# temperatureSensor.net
KiCad netlist of a schematic drawn in Altium Designer
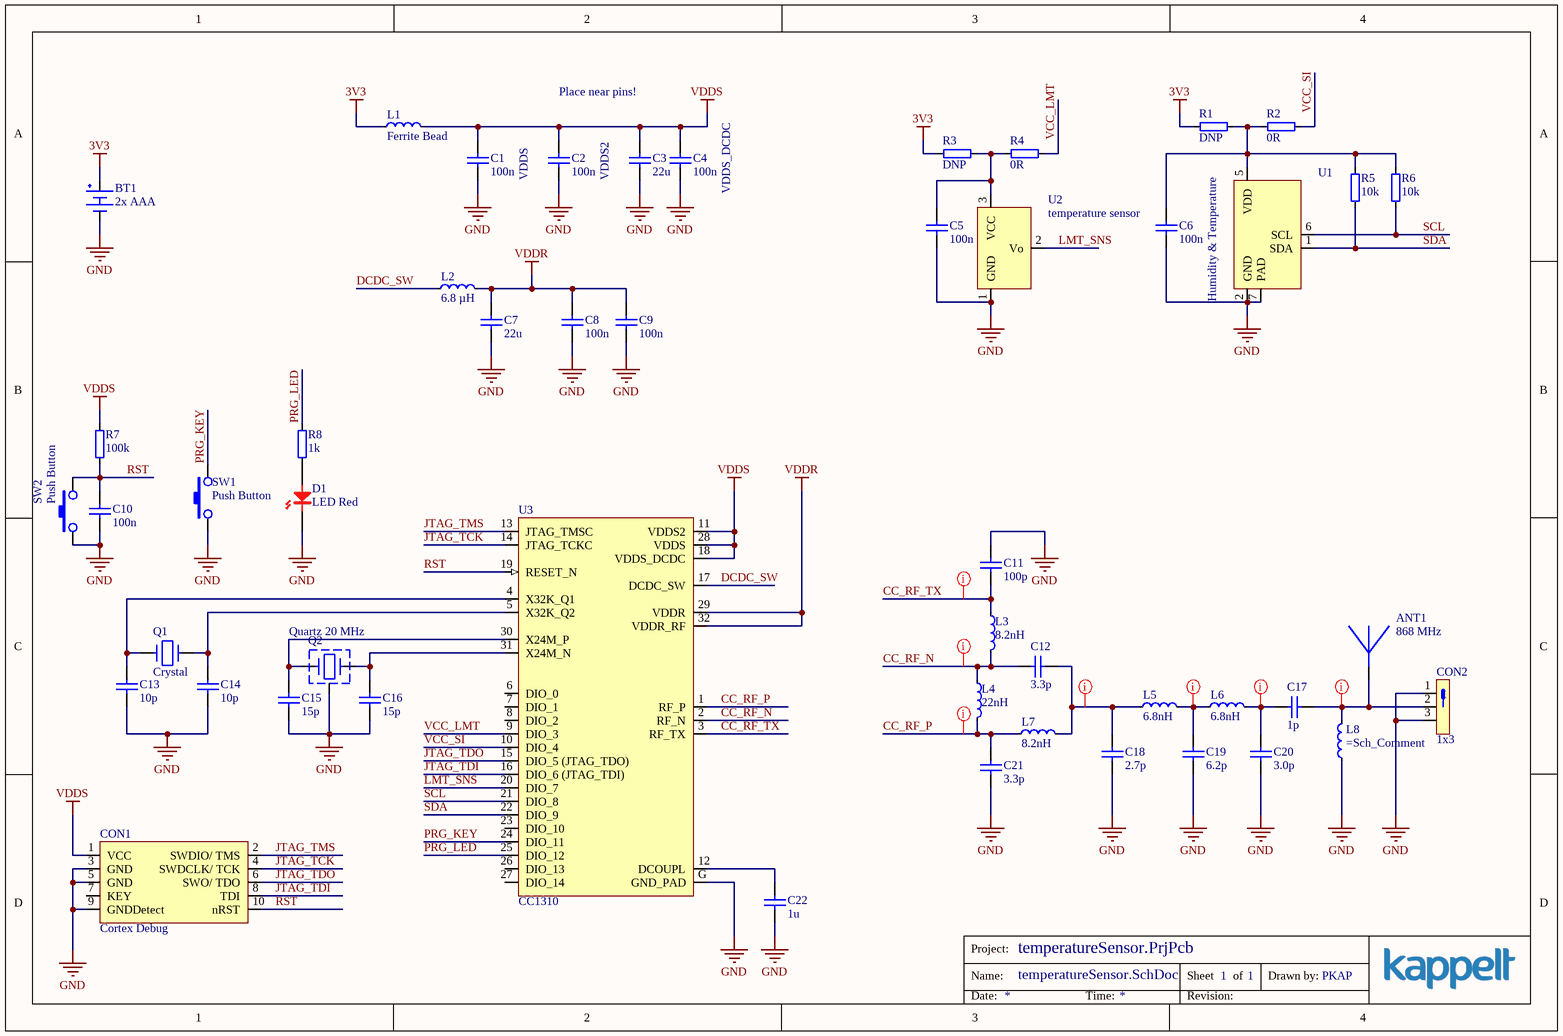
[diagram p0: temperatureSensor.SchDoc]

(export (version "E")
  (design (tool "Eeschema 10.0.6"))
  (components
    (comp (ref "ANT1")
      (value "868 MHz")
      (footprint "temperatureSensor:Ant-868-Helical")
      (description "868 MHz Helical PCB Antenna, see TI swra416.pdf")
      (libsource (lib "temperatureSensor") (part "ANT-868-Helical"))
    )
    (comp (ref "BT1")
      (value "2x AAA")
      (footprint "temperatureSensor:Keystone-2468")
      (description "Double AAA Battery Holder")
      (libsource (lib "temperatureSensor") (part "Battery-AAA-Double"))
    )
    (comp (ref "C1")
      (value "100n")
      (footprint "0603_N")
      (description "100n 50V 0603")
      (fields (field (name "PART NUMBER") "100n_50V_0603"))
      (libsource (lib "kappelt_altlib") (part "CAP_CERAMIC"))
    )
    (comp (ref "C2")
      (value "100n")
      (footprint "0603_N")
      (description "100n 50V 0603")
      (fields (field (name "PART NUMBER") "100n_50V_0603"))
      (libsource (lib "kappelt_altlib") (part "CAP_CERAMIC"))
    )
    (comp (ref "C3")
      (value "22u")
      (footprint "0805_N")
      (description "22u 25V 0805")
      (fields (field (name "PART NUMBER") "22u_25V_0805"))
      (libsource (lib "kappelt_altlib") (part "CAP_CERAMIC"))
    )
    (comp (ref "C4")
      (value "100n")
      (footprint "0603_N")
      (description "100n 50V 0603")
      (fields (field (name "PART NUMBER") "100n_50V_0603"))
      (libsource (lib "kappelt_altlib") (part "CAP_CERAMIC"))
    )
    (comp (ref "C5")
      (value "100n")
      (footprint "0603_N")
      (description "100n 50V 0603")
      (fields (field (name "PART NUMBER") "100n_50V_0603"))
      (libsource (lib "kappelt_altlib") (part "CAP_CERAMIC"))
    )
    (comp (ref "C6")
      (value "100n")
      (footprint "0603_N")
      (description "100n 50V 0603")
      (fields (field (name "PART NUMBER") "100n_50V_0603"))
      (libsource (lib "kappelt_altlib") (part "CAP_CERAMIC"))
    )
    (comp (ref "C7")
      (value "22u")
      (footprint "0805_N")
      (description "22u 25V 0805")
      (fields (field (name "PART NUMBER") "22u_25V_0805"))
      (libsource (lib "kappelt_altlib") (part "CAP_CERAMIC"))
    )
    (comp (ref "C8")
      (value "100n")
      (footprint "0603_N")
      (description "100n 50V 0603")
      (fields (field (name "PART NUMBER") "100n_50V_0603"))
      (libsource (lib "kappelt_altlib") (part "CAP_CERAMIC"))
    )
    (comp (ref "C9")
      (value "100n")
      (footprint "0603_N")
      (description "100n 50V 0603")
      (fields (field (name "PART NUMBER") "100n_50V_0603"))
      (libsource (lib "kappelt_altlib") (part "CAP_CERAMIC"))
    )
    (comp (ref "C10")
      (value "100n")
      (footprint "0603_N")
      (description "100n 50V 0603")
      (fields (field (name "PART NUMBER") "100n_50V_0603"))
      (libsource (lib "kappelt_altlib") (part "CAP_CERAMIC"))
    )
    (comp (ref "C11")
      (value "100p")
      (footprint "0603_N")
      (description "100p 50V 0603")
      (fields (field (name "PART NUMBER") "100p_50V_0603"))
      (libsource (lib "kappelt_altlib") (part "CAP_CERAMIC"))
    )
    (comp (ref "C12")
      (value "3.3p")
      (footprint "0603_N")
      (description "3p3 50V 0603")
      (fields (field (name "PART NUMBER") "3p3_50V_0603"))
      (libsource (lib "kappelt_altlib") (part "CAP_CERAMIC"))
    )
    (comp (ref "C13")
      (value "10p")
      (footprint "0603_N")
      (description "10p 50V 0603")
      (fields (field (name "PART NUMBER") "10p_50V_0603"))
      (libsource (lib "kappelt_altlib") (part "CAP_CERAMIC"))
    )
    (comp (ref "C14")
      (value "10p")
      (footprint "0603_N")
      (description "10p 50V 0603")
      (fields (field (name "PART NUMBER") "10p_50V_0603"))
      (libsource (lib "kappelt_altlib") (part "CAP_CERAMIC"))
    )
    (comp (ref "C15")
      (value "15p")
      (footprint "0805_N")
      (description "15p 50V 0805")
      (fields (field (name "PART NUMBER") "15p_50V_0805"))
      (libsource (lib "kappelt_altlib") (part "CAP_CERAMIC"))
    )
    (comp (ref "C16")
      (value "15p")
      (footprint "0805_N")
      (description "15p 50V 0805")
      (fields (field (name "PART NUMBER") "15p_50V_0805"))
      (libsource (lib "kappelt_altlib") (part "CAP_CERAMIC"))
    )
    (comp (ref "C17")
      (value "1p")
      (footprint "0603_N")
      (description "1p 50V 0603")
      (fields (field (name "PART NUMBER") "1p_50V_0603"))
      (libsource (lib "kappelt_altlib") (part "CAP_CERAMIC"))
    )
    (comp (ref "C18")
      (value "2.7p")
      (footprint "0603_N")
      (description "2p7 50V 0603")
      (fields (field (name "PART NUMBER") "2p7_50V_0603"))
      (libsource (lib "kappelt_altlib") (part "CAP_CERAMIC"))
    )
    (comp (ref "C19")
      (value "6.2p")
      (footprint "0603_N")
      (description "6p2 50V 0603")
      (fields (field (name "PART NUMBER") "6p2_50V_0603"))
      (libsource (lib "kappelt_altlib") (part "CAP_CERAMIC"))
    )
    (comp (ref "C20")
      (value "3.0p")
      (footprint "0603_N")
      (description "3p 50V 0603")
      (fields (field (name "PART NUMBER") "3p_50V_0603"))
      (libsource (lib "kappelt_altlib") (part "CAP_CERAMIC"))
    )
    (comp (ref "C21")
      (value "3.3p")
      (footprint "0603_N")
      (description "3p3 50V 0603")
      (fields (field (name "PART NUMBER") "3p3_50V_0603"))
      (libsource (lib "kappelt_altlib") (part "CAP_CERAMIC"))
    )
    (comp (ref "C22")
      (value "1u")
      (footprint "0603_N")
      (description "1u 50V 0603")
      (fields (field (name "PART NUMBER") "1u_50V_0603"))
      (libsource (lib "kappelt_altlib") (part "CAP_CERAMIC"))
    )
    (comp (ref "CON1")
      (value "Cortex Debug")
      (footprint "temperatureSensor:cortex-dbg")
      (libsource (lib "temperatureSensor") (part "Cortex-DBG"))
    )
    (comp (ref "CON2")
      (value "1x3")
      (footprint "Header_254_1x3_male")
      (description "Male Connector 1x3")
      (fields (field (name "PART NUMBER") "Header_1x03_male"))
      (libsource (lib "kappelt_altlib") (part "Header_1X03_male"))
    )
    (comp (ref "D1")
      (value "LED Red")
      (footprint "temperatureSensor:0805_LED")
      (description "Standard LED Red 0805")
      (libsource (lib "temperatureSensor") (part "LED-STD-RED-0805"))
    )
    (comp (ref "L1")
      (value "Ferrite Bead")
      (footprint "temperatureSensor:0603_N")
      (libsource (lib "") (part "Inductor_General_Purpose_0603_1"))
    )
    (comp (ref "L2")
      (value "6.8 µH")
      (footprint "temperatureSensor:0805_N")
      (description "Chip Inductor 0805")
      (libsource (lib "") (part "Inductor_General_Purpose_0603_1"))
    )
    (comp (ref "L3")
      (value "8.2nH")
      (footprint "temperatureSensor:0603_N")
      (description "8.2nH Inductor")
      (libsource (lib "temperatureSensor") (part "Inductor_General_Purpose_0603"))
    )
    (comp (ref "L4")
      (value "22nH")
      (footprint "temperatureSensor:0603_N")
      (description "22nH Inductor")
      (libsource (lib "temperatureSensor") (part "Inductor_General_Purpose_0603"))
    )
    (comp (ref "L5")
      (value "6.8nH")
      (footprint "temperatureSensor:0603_N")
      (description "6.8H Inductor")
      (libsource (lib "") (part "Inductor_General_Purpose_0603_1"))
    )
    (comp (ref "L6")
      (value "6.8nH")
      (footprint "temperatureSensor:0603_N")
      (description "6.8H Inductor")
      (libsource (lib "") (part "Inductor_General_Purpose_0603_1"))
    )
    (comp (ref "L7")
      (value "8.2nH")
      (footprint "temperatureSensor:0603_N")
      (description "8.2nH Inductor")
      (libsource (lib "") (part "Inductor_General_Purpose_0603_1"))
    )
    (comp (ref "L8")
      (value "~")
      (footprint "temperatureSensor:0603_N")
      (description "Inductor for PCB Antenna compensation")
      (libsource (lib "temperatureSensor") (part "Inductor_General_Purpose_0603"))
    )
    (comp (ref "Q1")
      (value "Crystal")
      (footprint "temperatureSensor:AB38t")
      (description "AB38T-32.768KHZ")
      (libsource (lib "temperatureSensor") (part "AB38T-32.768KHZ"))
    )
    (comp (ref "Q2")
      (value "Quartz 20 MHz")
      (footprint "temperatureSensor:LFXTAL058124")
      (libsource (lib "temperatureSensor") (part "LFXTAL058124"))
    )
    (comp (ref "R1")
      (value "DNP")
      (footprint "0603_N")
      (description "0R 100mW 0603")
      (fields (field (name "PART NUMBER") "0R_100mW_0603"))
      (libsource (lib "kappelt_altlib") (part "RESISTOR"))
    )
    (comp (ref "R2")
      (value "0R")
      (footprint "0603_N")
      (description "0R 100mW 0603")
      (fields (field (name "PART NUMBER") "0R_100mW_0603"))
      (libsource (lib "kappelt_altlib") (part "RESISTOR"))
    )
    (comp (ref "R3")
      (value "DNP")
      (footprint "0603_N")
      (description "0R 100mW 0603")
      (fields (field (name "PART NUMBER") "0R_100mW_0603"))
      (libsource (lib "kappelt_altlib") (part "RESISTOR"))
    )
    (comp (ref "R4")
      (value "0R")
      (footprint "0603_N")
      (description "0R 100mW 0603")
      (fields (field (name "PART NUMBER") "0R_100mW_0603"))
      (libsource (lib "kappelt_altlib") (part "RESISTOR"))
    )
    (comp (ref "R5")
      (value "10k")
      (footprint "0805_N")
      (description "10k 125mW 0805")
      (fields (field (name "PART NUMBER") "10k_125mW_0805"))
      (libsource (lib "kappelt_altlib") (part "RESISTOR"))
    )
    (comp (ref "R6")
      (value "10k")
      (footprint "0805_N")
      (description "10k 125mW 0805")
      (fields (field (name "PART NUMBER") "10k_125mW_0805"))
      (libsource (lib "kappelt_altlib") (part "RESISTOR"))
    )
    (comp (ref "R7")
      (value "100k")
      (footprint "0603_N")
      (description "100k 100mW 0603")
      (fields (field (name "PART NUMBER") "100k_100mW_0603"))
      (libsource (lib "kappelt_altlib") (part "RESISTOR"))
    )
    (comp (ref "R8")
      (value "1k")
      (footprint "0603_N")
      (description "1k 100mW 0603")
      (fields (field (name "PART NUMBER") "1k_100mW_0603"))
      (libsource (lib "kappelt_altlib") (part "RESISTOR"))
    )
    (comp (ref "SW1")
      (value "Push Button")
      (footprint "temperatureSensor:FSMSM")
      (description "Taster, Nicht beleuchtet, 24 V, 50 mA, 180 gf, Baureihe FSMSM, AlcoSwitch")
      (libsource (lib "temperatureSensor") (part "Switch-FSMSM"))
    )
    (comp (ref "SW2")
      (value "Push Button")
      (footprint "temperatureSensor:FSMSM")
      (description "Taster, Nicht beleuchtet, 24 V, 50 mA, 180 gf, Baureihe FSMSM, AlcoSwitch")
      (libsource (lib "temperatureSensor") (part "Switch-FSMSM"))
    )
    (comp (ref "U1")
      (value "Humidity & Temperature")
      (footprint "temperatureSensor:SI7020-DFN6")
      (description "I2C HUMIDITY AND TEMPERATURE SENSOR")
      (libsource (lib "temperatureSensor") (part "SI7020"))
    )
    (comp (ref "U2")
      (value "temperature sensor")
      (footprint "temperatureSensor:LMT85-TO92")
      (description "Analog Temperature Sensors with Class-AB Output")
      (libsource (lib "temperatureSensor") (part "LMT85-TO92"))
    )
    (comp (ref "U3")
      (value "CC1310")
      (footprint "temperatureSensor:CC1310F128RHB-QFN32")
      (description "CC1310 SimpleLink™ Ultra-Low-Power Sub-1 GHz Wireless MCU")
      (libsource (lib "temperatureSensor") (part "CC1310F128RHB"))
    )
  )
  (nets
    (net (code "1") (name "/CC_RF_N") (class "Default")
      (node (ref "C12") (pin "2") (pinfunction "2_2") (pintype "passive"))
      (node (ref "L3") (pin "2") (pinfunction "2_2") (pintype "passive"))
      (node (ref "L4") (pin "1") (pinfunction "1_1") (pintype "passive"))
      (node (ref "U3") (pin "2") (pinfunction "RF_N_2") (pintype "bidirectional"))
    )
    (net (code "2") (name "/CC_RF_P") (class "Default")
      (node (ref "C21") (pin "2") (pinfunction "2_2") (pintype "passive"))
      (node (ref "L4") (pin "2") (pinfunction "2_2") (pintype "passive"))
      (node (ref "L7") (pin "1") (pinfunction "1_1") (pintype "passive"))
      (node (ref "U3") (pin "1") (pinfunction "RF_P_1") (pintype "bidirectional"))
    )
    (net (code "3") (name "/CC_RF_TX") (class "Default")
      (node (ref "C11") (pin "1") (pinfunction "1_1") (pintype "passive"))
      (node (ref "L3") (pin "1") (pinfunction "1_1") (pintype "passive"))
      (node (ref "U3") (pin "3") (pinfunction "RF_TX_3") (pintype "bidirectional"))
    )
    (net (code "4") (name "/DCDC_SW") (class "Default")
      (node (ref "L2") (pin "1") (pinfunction "1_1") (pintype "passive"))
      (node (ref "U3") (pin "17") (pinfunction "DCDC_SW_17") (pintype "power_in"))
    )
    (net (code "5") (name "/JTAG_TCK") (class "Default")
      (node (ref "CON1") (pin "4") (pinfunction "SWDCLK/_TCK_4") (pintype "passive"))
      (node (ref "U3") (pin "14") (pinfunction "JTAG_TCKC_14") (pintype "bidirectional"))
    )
    (net (code "6") (name "/JTAG_TDI") (class "Default")
      (node (ref "CON1") (pin "8") (pinfunction "TDI_8") (pintype "passive"))
      (node (ref "U3") (pin "16") (pinfunction "DIO_6_(JTAG_TDI)_16") (pintype "bidirectional"))
    )
    (net (code "7") (name "/JTAG_TDO") (class "Default")
      (node (ref "CON1") (pin "6") (pinfunction "SWO/_TDO_6") (pintype "passive"))
      (node (ref "U3") (pin "15") (pinfunction "DIO_5_(JTAG_TDO)_15") (pintype "bidirectional"))
    )
    (net (code "8") (name "/JTAG_TMS") (class "Default")
      (node (ref "CON1") (pin "2") (pinfunction "SWDIO/_TMS_2") (pintype "passive"))
      (node (ref "U3") (pin "13") (pinfunction "JTAG_TMSC_13") (pintype "bidirectional"))
    )
    (net (code "9") (name "/LMT_SNS") (class "Default")
      (node (ref "U2") (pin "2") (pinfunction "Vo_2") (pintype "passive"))
      (node (ref "U3") (pin "20") (pinfunction "DIO_7_20") (pintype "bidirectional"))
    )
    (net (code "10") (name "/PRG_KEY") (class "Default")
      (node (ref "SW1") (pin "2") (pinfunction "NO2A_2") (pintype "passive"))
      (node (ref "U3") (pin "24") (pinfunction "DIO_11_24") (pintype "bidirectional"))
    )
    (net (code "11") (name "/PRG_LED") (class "Default")
      (node (ref "R8") (pin "1") (pintype "passive"))
      (node (ref "U3") (pin "25") (pinfunction "DIO_12_25") (pintype "bidirectional"))
    )
    (net (code "12") (name "/RST") (class "Default")
      (node (ref "C10") (pin "2") (pinfunction "2_2") (pintype "passive"))
      (node (ref "CON1") (pin "10") (pinfunction "nRST_10") (pintype "passive"))
      (node (ref "R7") (pin "2") (pintype "passive"))
      (node (ref "SW2") (pin "2") (pinfunction "NO2A_2") (pintype "passive"))
      (node (ref "U3") (pin "19") (pinfunction "RESET_N_19") (pintype "input"))
    )
    (net (code "13") (name "/SCL") (class "Default")
      (node (ref "R6") (pin "2") (pintype "passive"))
      (node (ref "U1") (pin "6") (pinfunction "SCL_6") (pintype "passive"))
      (node (ref "U3") (pin "21") (pinfunction "DIO_8_21") (pintype "bidirectional"))
    )
    (net (code "14") (name "/SDA") (class "Default")
      (node (ref "R5") (pin "2") (pintype "passive"))
      (node (ref "U1") (pin "1") (pinfunction "SDA_1") (pintype "passive"))
      (node (ref "U3") (pin "22") (pinfunction "DIO_9_22") (pintype "bidirectional"))
    )
    (net (code "15") (name "/VCC_LMT") (class "Default")
      (node (ref "R4") (pin "2") (pintype "passive"))
      (node (ref "U3") (pin "9") (pinfunction "DIO_3_9") (pintype "bidirectional"))
    )
    (net (code "16") (name "/VCC_SI") (class "Default")
      (node (ref "R2") (pin "2") (pintype "passive"))
      (node (ref "U3") (pin "10") (pinfunction "DIO_4_10") (pintype "bidirectional"))
    )
    (net (code "17") (name "3V3") (class "Default")
      (node (ref "BT1") (pin "P") (pinfunction "+_P") (pintype "passive"))
      (node (ref "L1") (pin "1") (pinfunction "1_1") (pintype "passive"))
      (node (ref "R1") (pin "1") (pintype "passive"))
      (node (ref "R3") (pin "1") (pintype "passive"))
    )
    (net (code "18") (name "GND") (class "Default")
      (node (ref "BT1") (pin "N") (pinfunction "-_N") (pintype "passive"))
      (node (ref "C1") (pin "1") (pinfunction "1_1") (pintype "passive"))
      (node (ref "C10") (pin "1") (pinfunction "1_1") (pintype "passive"))
      (node (ref "C11") (pin "2") (pinfunction "2_2") (pintype "passive"))
      (node (ref "C13") (pin "1") (pinfunction "1_1") (pintype "passive"))
      (node (ref "C14") (pin "1") (pinfunction "1_1") (pintype "passive"))
      (node (ref "C15") (pin "1") (pinfunction "1_1") (pintype "passive"))
      (node (ref "C16") (pin "1") (pinfunction "1_1") (pintype "passive"))
      (node (ref "C18") (pin "2") (pinfunction "2_2") (pintype "passive"))
      (node (ref "C19") (pin "2") (pinfunction "2_2") (pintype "passive"))
      (node (ref "C2") (pin "1") (pinfunction "1_1") (pintype "passive"))
      (node (ref "C20") (pin "2") (pinfunction "2_2") (pintype "passive"))
      (node (ref "C21") (pin "1") (pinfunction "1_1") (pintype "passive"))
      (node (ref "C22") (pin "1") (pinfunction "1_1") (pintype "passive"))
      (node (ref "C3") (pin "1") (pinfunction "1_1") (pintype "passive"))
      (node (ref "C4") (pin "1") (pinfunction "1_1") (pintype "passive"))
      (node (ref "C5") (pin "1") (pinfunction "1_1") (pintype "passive"))
      (node (ref "C6") (pin "1") (pinfunction "1_1") (pintype "passive"))
      (node (ref "C7") (pin "1") (pinfunction "1_1") (pintype "passive"))
      (node (ref "C8") (pin "1") (pinfunction "1_1") (pintype "passive"))
      (node (ref "C9") (pin "1") (pinfunction "1_1") (pintype "passive"))
      (node (ref "CON1") (pin "3") (pinfunction "GND_3") (pintype "passive"))
      (node (ref "CON1") (pin "5") (pinfunction "GND_5") (pintype "passive"))
      (node (ref "CON1") (pin "9") (pinfunction "GNDDetect_9") (pintype "passive"))
      (node (ref "CON2") (pin "1") (pinfunction "1_1") (pintype "passive"))
      (node (ref "CON2") (pin "3") (pinfunction "3_3") (pintype "passive"))
      (node (ref "D1") (pin "K") (pinfunction "K_K") (pintype "passive"))
      (node (ref "L8") (pin "1") (pinfunction "1_1") (pintype "passive"))
      (node (ref "Q2") (pin "G") (pinfunction "GND_G") (pintype "passive"))
      (node (ref "SW1") (pin "1") (pinfunction "NO1A_1") (pintype "passive"))
      (node (ref "SW2") (pin "1") (pinfunction "NO1A_1") (pintype "passive"))
      (node (ref "U1") (pin "2") (pinfunction "GND_2") (pintype "passive"))
      (node (ref "U1") (pin "7") (pinfunction "PAD_7") (pintype "passive"))
      (node (ref "U2") (pin "1") (pinfunction "GND_1") (pintype "passive"))
      (node (ref "U3") (pin "G") (pinfunction "GND_PAD_G") (pintype "power_in"))
    )
    (net (code "19") (name "Net-(ANT1-Pad1)") (class "Default")
      (node (ref "ANT1") (pin "1") (pinfunction "1_1") (pintype "passive"))
      (node (ref "C17") (pin "1") (pinfunction "1_1") (pintype "passive"))
      (node (ref "CON2") (pin "2") (pinfunction "2_2") (pintype "passive"))
      (node (ref "L8") (pin "2") (pinfunction "2_2") (pintype "passive"))
    )
    (net (code "20") (name "Net-(C12-Pad1)") (class "Default")
      (node (ref "C12") (pin "1") (pinfunction "1_1") (pintype "passive"))
      (node (ref "C18") (pin "1") (pinfunction "1_1") (pintype "passive"))
      (node (ref "L5") (pin "1") (pinfunction "1_1") (pintype "passive"))
      (node (ref "L7") (pin "2") (pinfunction "2_2") (pintype "passive"))
    )
    (net (code "21") (name "Net-(C17-Pad2)") (class "Default")
      (node (ref "C17") (pin "2") (pinfunction "2_2") (pintype "passive"))
      (node (ref "C20") (pin "1") (pinfunction "1_1") (pintype "passive"))
      (node (ref "L6") (pin "2") (pinfunction "2_2") (pintype "passive"))
    )
    (net (code "22") (name "Net-(C19-Pad1)") (class "Default")
      (node (ref "C19") (pin "1") (pinfunction "1_1") (pintype "passive"))
      (node (ref "L5") (pin "2") (pinfunction "2_2") (pintype "passive"))
      (node (ref "L6") (pin "1") (pinfunction "1_1") (pintype "passive"))
    )
    (net (code "23") (name "Net-(D1-PadA)") (class "Default")
      (node (ref "D1") (pin "A") (pinfunction "A_A") (pintype "passive"))
      (node (ref "R8") (pin "2") (pintype "passive"))
    )
    (net (code "24") (name "Net-(U1-VDD)") (class "Default")
      (node (ref "C6") (pin "2") (pinfunction "2_2") (pintype "passive"))
      (node (ref "R1") (pin "2") (pintype "passive"))
      (node (ref "R2") (pin "1") (pintype "passive"))
      (node (ref "R5") (pin "1") (pintype "passive"))
      (node (ref "R6") (pin "1") (pintype "passive"))
      (node (ref "U1") (pin "5") (pinfunction "VDD_5") (pintype "passive"))
    )
    (net (code "25") (name "Net-(U2-VCC)") (class "Default")
      (node (ref "C5") (pin "2") (pinfunction "2_2") (pintype "passive"))
      (node (ref "R3") (pin "2") (pintype "passive"))
      (node (ref "R4") (pin "1") (pintype "passive"))
      (node (ref "U2") (pin "3") (pinfunction "VCC_3") (pintype "passive"))
    )
    (net (code "26") (name "Net-(U3-DCOUPL)") (class "Default")
      (node (ref "C22") (pin "2") (pinfunction "2_2") (pintype "passive"))
      (node (ref "U3") (pin "12") (pinfunction "DCOUPL_12") (pintype "power_in"))
    )
    (net (code "27") (name "Net-(U3-X24M_N)") (class "Default")
      (node (ref "C16") (pin "2") (pinfunction "2_2") (pintype "passive"))
      (node (ref "Q2") (pin "Q1") (pintype "passive"))
      (node (ref "U3") (pin "31") (pinfunction "X24M_N_31") (pintype "bidirectional"))
    )
    (net (code "28") (name "Net-(U3-X24M_P)") (class "Default")
      (node (ref "C15") (pin "2") (pinfunction "2_2") (pintype "passive"))
      (node (ref "Q2") (pin "Q2") (pintype "passive"))
      (node (ref "U3") (pin "30") (pinfunction "X24M_P_30") (pintype "bidirectional"))
    )
    (net (code "29") (name "Net-(U3-X32K_Q1)") (class "Default")
      (node (ref "C13") (pin "2") (pinfunction "2_2") (pintype "passive"))
      (node (ref "Q1") (pin "1") (pintype "passive"))
      (node (ref "U3") (pin "4") (pinfunction "X32K_Q1_4") (pintype "bidirectional"))
    )
    (net (code "30") (name "Net-(U3-X32K_Q2)") (class "Default")
      (node (ref "C14") (pin "2") (pinfunction "2_2") (pintype "passive"))
      (node (ref "Q1") (pin "2") (pintype "passive"))
      (node (ref "U3") (pin "5") (pinfunction "X32K_Q2_5") (pintype "bidirectional"))
    )
    (net (code "31") (name "VDDR") (class "Default")
      (node (ref "C7") (pin "2") (pinfunction "2_2") (pintype "passive"))
      (node (ref "C8") (pin "2") (pinfunction "2_2") (pintype "passive"))
      (node (ref "C9") (pin "2") (pinfunction "2_2") (pintype "passive"))
      (node (ref "L2") (pin "2") (pinfunction "2_2") (pintype "passive"))
      (node (ref "U3") (pin "29") (pinfunction "VDDR_29") (pintype "power_in"))
      (node (ref "U3") (pin "32") (pinfunction "VDDR_RF_32") (pintype "power_in"))
    )
    (net (code "32") (name "VDDS") (class "Default")
      (node (ref "C1") (pin "2") (pinfunction "2_2") (pintype "passive"))
      (node (ref "C2") (pin "2") (pinfunction "2_2") (pintype "passive"))
      (node (ref "C3") (pin "2") (pinfunction "2_2") (pintype "passive"))
      (node (ref "C4") (pin "2") (pinfunction "2_2") (pintype "passive"))
      (node (ref "CON1") (pin "1") (pinfunction "VCC_1") (pintype "passive"))
      (node (ref "L1") (pin "2") (pinfunction "2_2") (pintype "passive"))
      (node (ref "R7") (pin "1") (pintype "passive"))
      (node (ref "U3") (pin "11") (pinfunction "VDDS2_11") (pintype "power_in"))
      (node (ref "U3") (pin "18") (pinfunction "VDDS_DCDC_18") (pintype "power_in"))
      (node (ref "U3") (pin "28") (pinfunction "VDDS_28") (pintype "power_in"))
    )
    (net (code "33") (name "unconnected-(CON1-KEY-Pad7)") (class "Default")
      (node (ref "CON1") (pin "7") (pinfunction "KEY_7") (pintype "passive"))
    )
    (net (code "34") (name "unconnected-(U3-DIO_0-Pad6)") (class "Default")
      (node (ref "U3") (pin "6") (pinfunction "DIO_0_6") (pintype "bidirectional"))
    )
    (net (code "35") (name "unconnected-(U3-DIO_1-Pad7)") (class "Default")
      (node (ref "U3") (pin "7") (pinfunction "DIO_1_7") (pintype "bidirectional"))
    )
    (net (code "36") (name "unconnected-(U3-DIO_2-Pad8)") (class "Default")
      (node (ref "U3") (pin "8") (pinfunction "DIO_2_8") (pintype "bidirectional"))
    )
    (net (code "37") (name "unconnected-(U3-DIO_10-Pad23)") (class "Default")
      (node (ref "U3") (pin "23") (pinfunction "DIO_10_23") (pintype "bidirectional"))
    )
    (net (code "38") (name "unconnected-(U3-DIO_13-Pad26)") (class "Default")
      (node (ref "U3") (pin "26") (pinfunction "DIO_13_26") (pintype "bidirectional"))
    )
    (net (code "39") (name "unconnected-(U3-DIO_14-Pad27)") (class "Default")
      (node (ref "U3") (pin "27") (pinfunction "DIO_14_27") (pintype "bidirectional"))
    )
  )
)
